# Mach_dieu_khien_tu_xa.net
KiCad netlist of a schematic drawn in Altium Designer
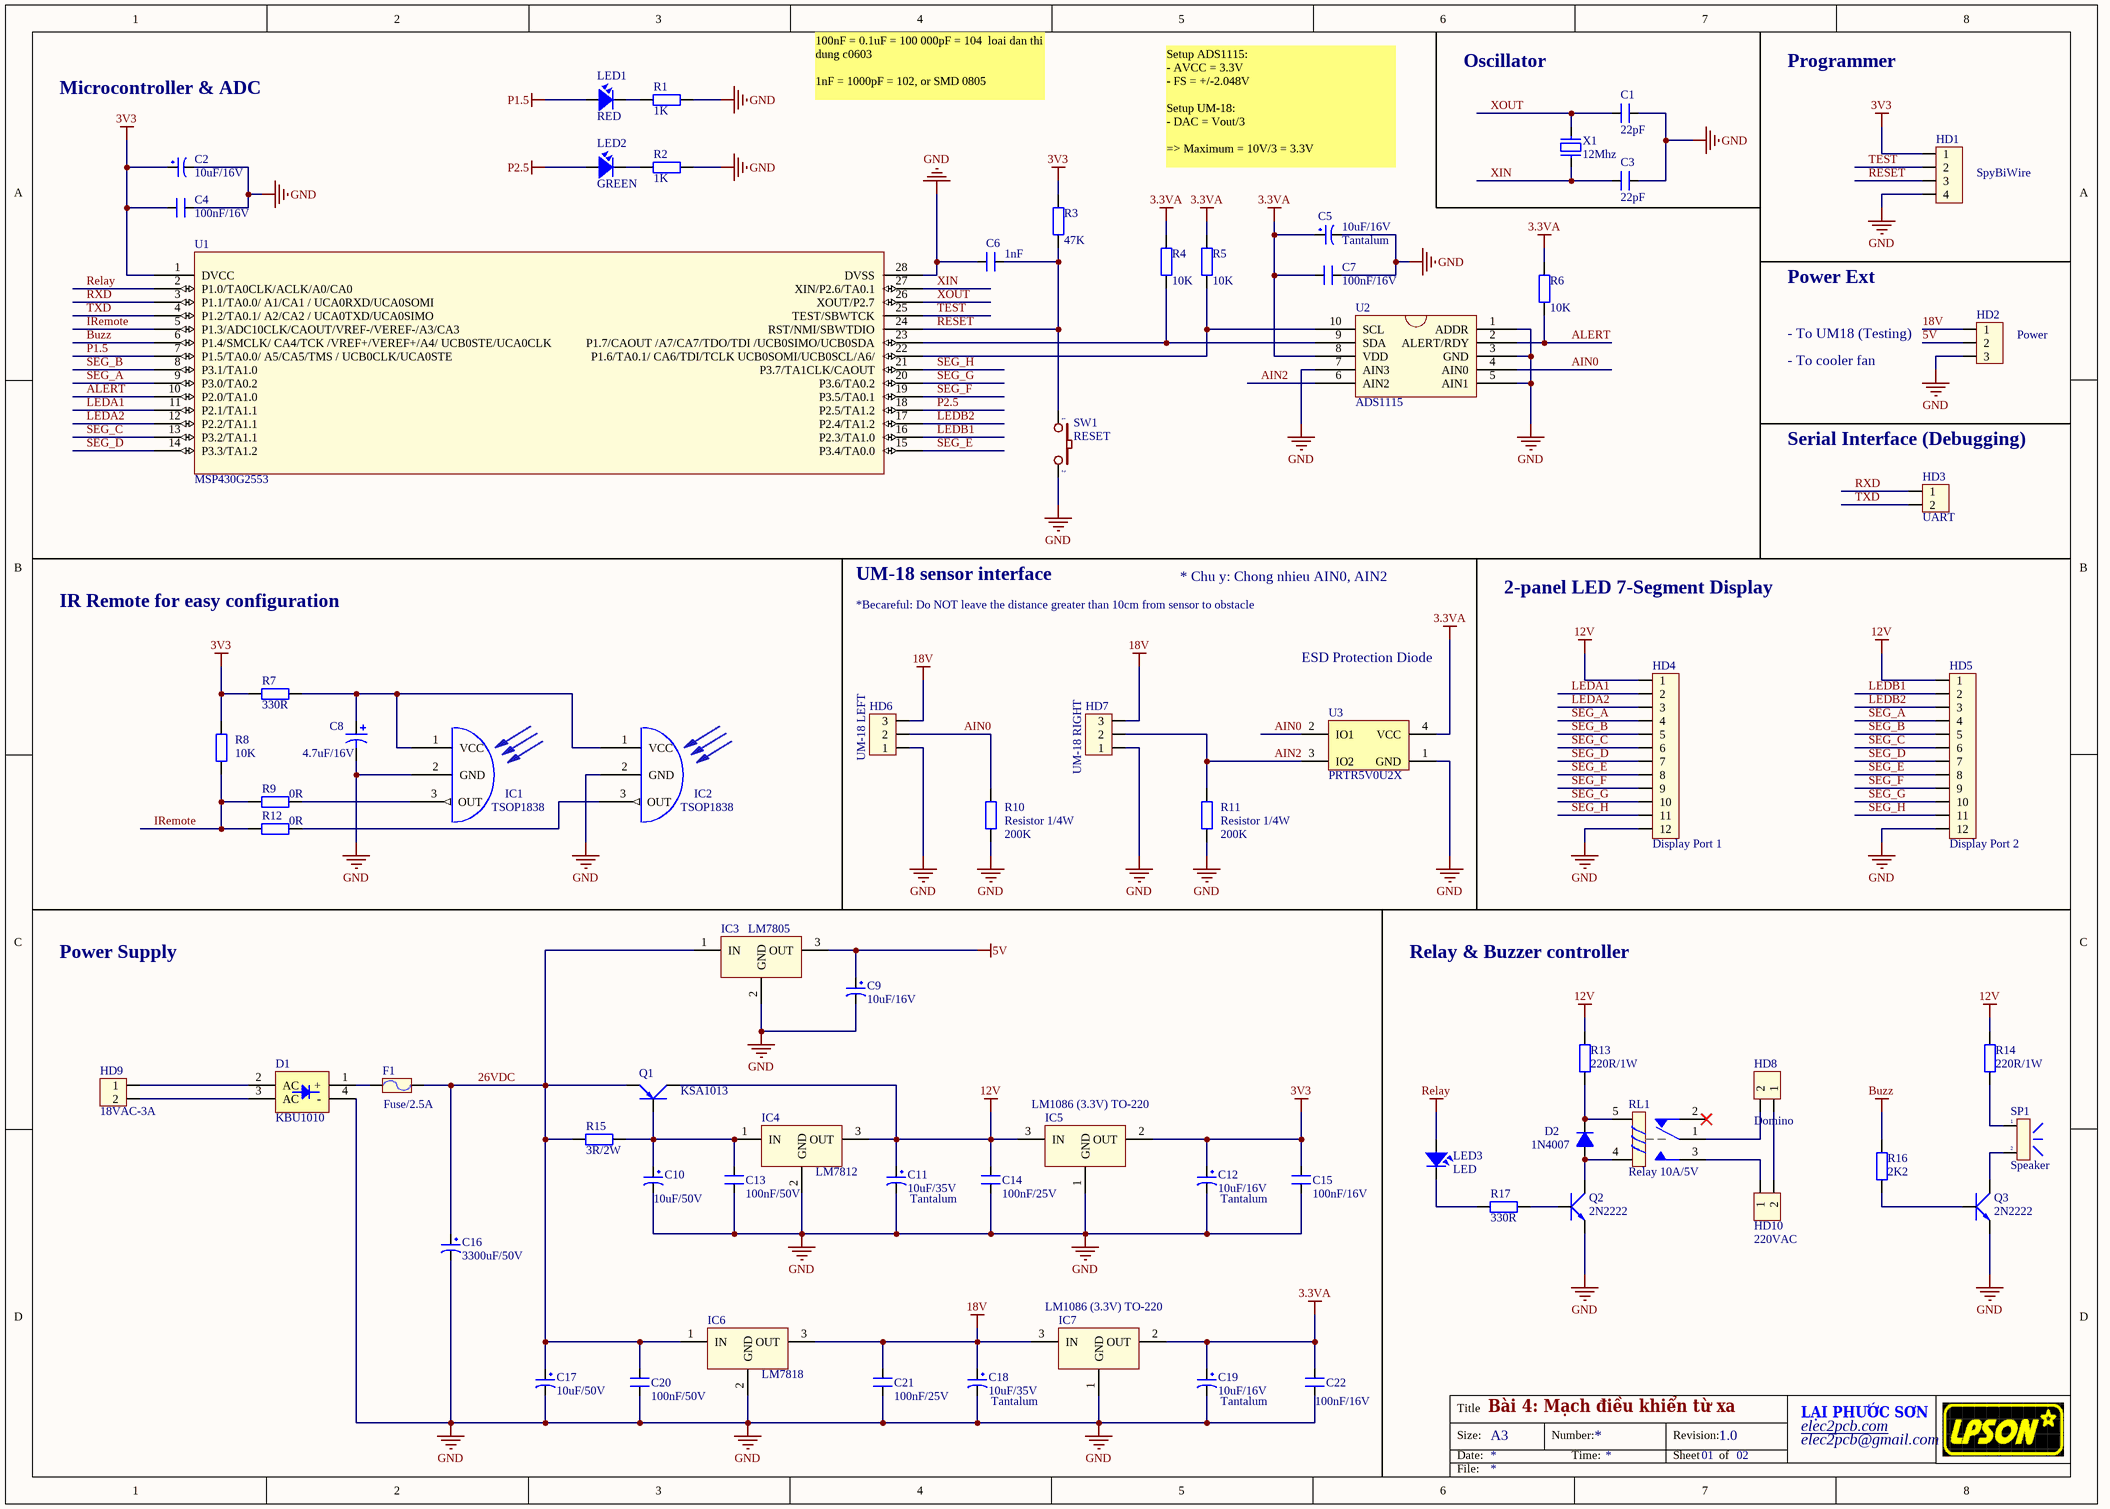
[diagram p0: Mach dieu khien tu xa.SchDoc]

(export (version "E")
  (design (tool "Eeschema 10.0.6"))
  (components
    (comp (ref "C1")
      (value "22pF")
      (footprint "C0603")
      (description "0805-SMD Capacitor")
      (libsource (lib "syhaunguyen") (part "CN1"))
    )
    (comp (ref "C2")
      (value "10uF/16V")
      (footprint "C0805")
      (description "Cap P  0,1uF < 22uF , 16 - 50V")
      (libsource (lib "") (part "CP1_1"))
    )
    (comp (ref "C3")
      (value "22pF")
      (footprint "C0603")
      (description "0805-SMD Capacitor")
      (libsource (lib "syhaunguyen") (part "CN1"))
    )
    (comp (ref "C4")
      (value "100nF/16V")
      (footprint "Tu gom 104")
      (description "Cap np 104 => 105pF")
      (libsource (lib "VNELEK") (part "CN2"))
    )
    (comp (ref "C5")
      (value "10uF/16V")
      (footprint "CAP_TANTA_10UF_16V")
      (description "Tantalum Capacitor")
      (fields (field (name "TYPE") "Tantalum"))
      (libsource (lib "") (part "CP1_1"))
    )
    (comp (ref "C6")
      (value "1nF")
      (footprint "C0805")
      (description "Cap np 104 => 105pF")
      (libsource (lib "VNELEK") (part "CN2"))
    )
    (comp (ref "C7")
      (value "100nF/16V")
      (footprint "Tu gom 104")
      (description "Cap np 104 => 105pF")
      (libsource (lib "VNELEK") (part "CN2"))
    )
    (comp (ref "C8")
      (value "4.7uF/16V")
      (footprint "C0805")
      (description "Polarized Capacitor (Radial)")
      (fields (field (name "Comment") "Cap Pol1") (field (name "PUBLISHER") "Altium Limited"))
      (libsource (lib "Miscellaneous Devices") (part "Cap Pol1"))
    )
    (comp (ref "C9")
      (value "10uF/16V")
      (footprint "CAP_10UF_16V")
      (description "Aluminium Capacitor")
      (libsource (lib "VNELEK") (part "CP1"))
    )
    (comp (ref "C10")
      (value "10uF/50V")
      (footprint "C_FC_10UF_50V")
      (description "Aluminium Capacitor")
      (libsource (lib "VNELEK") (part "CP1"))
    )
    (comp (ref "C11")
      (value "10uF/35V")
      (footprint "CAP_TANTA_10UF_35V")
      (description "Tantalum Capacitor")
      (fields (field (name "TYPE") "Tantalum"))
      (libsource (lib "VNELEK") (part "CP1"))
    )
    (comp (ref "C12")
      (value "10uF/16V")
      (footprint "CAP_TANTA_10UF_16V")
      (description "Tantalum Capacitor")
      (fields (field (name "TYPE") "Tantalum"))
      (libsource (lib "VNELEK") (part "CP1"))
    )
    (comp (ref "C13")
      (value "100nF/50V")
      (footprint "Tu gom 104")
      (description "Cap np 104 => 105pF")
      (libsource (lib "VNELEK") (part "CN2"))
    )
    (comp (ref "C14")
      (value "100nF/25V")
      (footprint "Tu gom 104")
      (description "Cap np 104 => 105pF")
      (libsource (lib "VNELEK") (part "CN2"))
    )
    (comp (ref "C15")
      (value "100nF/16V")
      (footprint "Tu gom 104")
      (description "Cap np 104 => 105pF")
      (libsource (lib "VNELEK") (part "CN2"))
    )
    (comp (ref "C16")
      (value "3300uF/50V")
      (footprint "CAP_3300UF_50V")
      (description "Cap P  0,1uF < 22uF , 16 - 50V")
      (libsource (lib "VNELEK") (part "CP1"))
    )
    (comp (ref "C17")
      (value "10uF/50V")
      (footprint "C_FC_10UF_50V")
      (description "Aluminium Capacitor")
      (libsource (lib "VNELEK") (part "CP1"))
    )
    (comp (ref "C18")
      (value "10uF/35V")
      (footprint "CAP_TANTA_10UF_35V")
      (description "Tantalum Capacitor")
      (fields (field (name "TYPE") "Tantalum"))
      (libsource (lib "VNELEK") (part "CP1"))
    )
    (comp (ref "C19")
      (value "10uF/16V")
      (footprint "CAP_TANTA_10UF_16V")
      (description "Tantalum Capacitor")
      (fields (field (name "TYPE") "Tantalum"))
      (libsource (lib "VNELEK") (part "CP1"))
    )
    (comp (ref "C20")
      (value "100nF/50V")
      (footprint "Tu gom 104")
      (description "Cap np 104 => 105pF")
      (libsource (lib "VNELEK") (part "CN2"))
    )
    (comp (ref "C21")
      (value "100nF/25V")
      (footprint "Tu gom 104")
      (description "Cap np 104 => 105pF")
      (libsource (lib "VNELEK") (part "CN2"))
    )
    (comp (ref "C22")
      (value "100nF/16V")
      (footprint "Tu gom 104")
      (description "Cap np 104 => 105pF")
      (libsource (lib "VNELEK") (part "CN2"))
    )
    (comp (ref "D1")
      (value "KBU1010")
      (footprint "KBU1010G")
      (description "10A glass passivated bridge rectifier")
      (libsource (lib "Tran Tuan") (part "KBU1010"))
    )
    (comp (ref "D2")
      (value "1N4007")
      (footprint "1N4007")
      (description "Diode 1A")
      (libsource (lib "VNELEK") (part "D1A"))
    )
    (comp (ref "F1")
      (value "Fuse/2.5A")
      (footprint "FUSE2_5A")
      (description "Fuse")
      (fields (field (name "DESIGNED BY") "VanDungEvn"))
      (libsource (lib "VNELEK") (part "Fuse"))
    )
    (comp (ref "HD1")
      (value "SpyBiWire")
      (footprint "Header_4")
      (description "Header 4 (Green)")
      (libsource (lib "VNELEK") (part "Hed4"))
    )
    (comp (ref "HD2")
      (value "Power")
      (footprint "CON3")
      (description "Header 3 (Green)")
      (libsource (lib "") (part "Hed3_1"))
    )
    (comp (ref "HD3")
      (value "UART")
      (footprint "Header_2")
      (description "Header 2 (Green)")
      (libsource (lib "") (part "Hed2_2"))
    )
    (comp (ref "HD4")
      (value "Display Port 1")
      (footprint "CON12")
      (description "Header 12")
      (libsource (lib "Tran Tuan") (part "Hed12"))
    )
    (comp (ref "HD5")
      (value "Display Port 2")
      (footprint "CON12")
      (description "Header 12")
      (libsource (lib "Tran Tuan") (part "Hed12"))
    )
    (comp (ref "HD6")
      (value "UM-18 LEFT")
      (footprint "CON3")
      (description "Header 3 (Green)")
      (libsource (lib "VNELEK") (part "Hed3"))
    )
    (comp (ref "HD7")
      (value "UM-18 RIGHT")
      (footprint "CON3")
      (description "Header 3 (Green)")
      (libsource (lib "VNELEK") (part "Hed3"))
    )
    (comp (ref "HD8")
      (value "Domino")
      (footprint "DOMINO2_GREEN")
      (description "Header 2 (Green)")
      (libsource (lib "") (part "Hed2_2"))
    )
    (comp (ref "HD9")
      (value "18VAC-3A")
      (footprint "DOMINO2_GREEN")
      (description "Header 2 (Green)")
      (libsource (lib "") (part "Hed2_1"))
    )
    (comp (ref "HD10")
      (value "220VAC")
      (footprint "DOMINO2_GREEN")
      (description "Header 2 (Green)")
      (libsource (lib "VNELEK") (part "Hed2"))
    )
    (comp (ref "IC1")
      (value "TSOP1838")
      (footprint "TSOP1838")
      (libsource (lib "Tran Tuan") (part "TSOP1838"))
    )
    (comp (ref "IC2")
      (value "TSOP1838")
      (footprint "TSOP1838")
      (libsource (lib "Tran Tuan") (part "TSOP1838"))
    )
    (comp (ref "IC3")
      (value "LM7805")
      (footprint "LM7805")
      (description "Linear Regulator")
      (libsource (lib "VNELEK") (part "LM78xx"))
    )
    (comp (ref "IC4")
      (value "LM7812")
      (footprint "LM7805")
      (description "Linear Regulator")
      (fields (field (name "MANUFACTURER") "Fairchild Semiconductor"))
      (libsource (lib "VNELEK") (part "LM78xx"))
    )
    (comp (ref "IC5")
      (value "LM1086 (3.3V) TO-220")
      (footprint "LM1086")
      (description "Linear Regulator")
      (libsource (lib "") (part "LM78xx_1"))
    )
    (comp (ref "IC6")
      (value "LM7818")
      (footprint "LM7805")
      (description "Linear Regulator")
      (libsource (lib "VNELEK") (part "LM78xx"))
    )
    (comp (ref "IC7")
      (value "LM1086 (3.3V) TO-220")
      (footprint "LM1086")
      (description "Linear Regulator")
      (libsource (lib "") (part "LM78xx_1"))
    )
    (comp (ref "LED1")
      (value "RED")
      (footprint "LED3R")
      (description "LED Single colour Green and Red")
      (libsource (lib "VNELEK") (part "LED"))
    )
    (comp (ref "LED2")
      (value "GREEN")
      (footprint "LED3R")
      (description "LED Single colour Green and Red")
      (libsource (lib "VNELEK") (part "LED"))
    )
    (comp (ref "LED3")
      (value "LED")
      (footprint "LED3R")
      (description "LED Single colour Green and Red")
      (libsource (lib "VNELEK") (part "LED"))
    )
    (comp (ref "Q1")
      (value "KSA1013")
      (footprint "KSA1013")
      (description "PNP 600mW, ECB")
      (fields (field (name "MANUFACTURER") "Fairchild Semiconductor"))
      (libsource (lib "VNELEK") (part "A1015"))
    )
    (comp (ref "Q2")
      (value "2N2222")
      (footprint "2N2222")
      (description "TRANS GP SS NPN LP 40V TO92")
      (libsource (lib "VNELEK") (part "C1815"))
    )
    (comp (ref "Q3")
      (value "2N2222")
      (footprint "2N2222")
      (description "TRANS GP SS NPN LP 40V TO92")
      (libsource (lib "VNELEK") (part "C1815"))
    )
    (comp (ref "R1")
      (value "1K")
      (footprint "RESC2012(0805)")
      (description "Resistor")
      (fields (field (name "Comment") "Res2") (field (name "PUBLISHER") "Altium Limited"))
      (libsource (lib "Miscellaneous Devices") (part "Res2"))
    )
    (comp (ref "R2")
      (value "1K")
      (footprint "RESC2012(0805)")
      (description "Resistor")
      (fields (field (name "Comment") "Res2") (field (name "PUBLISHER") "Altium Limited"))
      (libsource (lib "Miscellaneous Devices") (part "Res2"))
    )
    (comp (ref "R3")
      (value "47K")
      (footprint "RESC2012(0805)")
      (description "Resistor")
      (fields (field (name "Comment") "Res2") (field (name "PUBLISHER") "Altium Limited"))
      (libsource (lib "") (part "Res2_2"))
    )
    (comp (ref "R4")
      (value "10K")
      (footprint "RESC2012(0805)")
      (description "Resistor")
      (fields (field (name "Comment") "Res2") (field (name "PUBLISHER") "Altium Limited"))
      (libsource (lib "") (part "Res2_2"))
    )
    (comp (ref "R5")
      (value "10K")
      (footprint "RESC2012(0805)")
      (description "Resistor")
      (fields (field (name "Comment") "Res2") (field (name "PUBLISHER") "Altium Limited"))
      (libsource (lib "") (part "Res2_2"))
    )
    (comp (ref "R6")
      (value "10K")
      (footprint "RESC2012(0805)")
      (description "Resistor")
      (fields (field (name "Comment") "Res2") (field (name "PUBLISHER") "Altium Limited"))
      (libsource (lib "") (part "Res2_2"))
    )
    (comp (ref "R7")
      (value "330R")
      (footprint "RESC2012(0805)")
      (description "Resistor")
      (fields (field (name "Comment") "Res2") (field (name "PUBLISHER") "Altium Limited"))
      (libsource (lib "Miscellaneous Devices") (part "Res2"))
    )
    (comp (ref "R8")
      (value "10K")
      (footprint "RESC2012(0805)")
      (description "Resistor")
      (fields (field (name "Comment") "Res2") (field (name "PUBLISHER") "Altium Limited"))
      (libsource (lib "") (part "Res2_2"))
    )
    (comp (ref "R9")
      (value "0R")
      (footprint "RESC2012(0805)")
      (description "Resistor")
      (fields (field (name "Comment") "Res2") (field (name "PUBLISHER") "Altium Limited"))
      (libsource (lib "Miscellaneous Devices") (part "Res2"))
    )
    (comp (ref "R10")
      (value "Resistor 1/4W")
      (footprint "RESC2012(0805)")
      (fields (field (name "ALTIUM_VALUE") "200K"))
      (libsource (lib "") (part "Res2_1"))
    )
    (comp (ref "R11")
      (value "Resistor 1/4W")
      (footprint "RESC2012(0805)")
      (fields (field (name "ALTIUM_VALUE") "200K"))
      (libsource (lib "") (part "Res2_1"))
    )
    (comp (ref "R12")
      (value "0R")
      (footprint "RESC2012(0805)")
      (description "Resistor")
      (fields (field (name "Comment") "Res2") (field (name "PUBLISHER") "Altium Limited"))
      (libsource (lib "Miscellaneous Devices") (part "Res2"))
    )
    (comp (ref "R13")
      (value "220R/1W")
      (footprint "CFR1WS")
      (description "Resistor")
      (fields (field (name "Comment") "Res2") (field (name "PUBLISHER") "Altium Limited"))
      (libsource (lib "") (part "Res2_1"))
    )
    (comp (ref "R14")
      (value "220R/1W")
      (footprint "CFR1WS")
      (description "Resistor")
      (fields (field (name "Comment") "Res2") (field (name "PUBLISHER") "Altium Limited"))
      (libsource (lib "") (part "Res2_1"))
    )
    (comp (ref "R15")
      (value "3R/2W")
      (footprint "R2WD")
      (description "Resistor")
      (fields (field (name "Comment") "Res2") (field (name "PUBLISHER") "Altium Limited"))
      (libsource (lib "Miscellaneous Devices") (part "Res2"))
    )
    (comp (ref "R16")
      (value "2K2")
      (footprint "RES 1/4W CFR25")
      (description "Resistor")
      (fields (field (name "Comment") "Res2") (field (name "PUBLISHER") "Altium Limited"))
      (libsource (lib "") (part "Res2_1"))
    )
    (comp (ref "R17")
      (value "330R")
      (footprint "RES 1/4W CFR25")
      (description "Resistor")
      (fields (field (name "Comment") "Res2") (field (name "PUBLISHER") "Altium Limited"))
      (libsource (lib "Miscellaneous Devices") (part "Res2"))
    )
    (comp (ref "RL1")
      (value "Relay 10A/5V")
      (footprint "RL_10A_5V")
      (description "Relay SPDT,10A - 12VDC 5 Pin")
      (libsource (lib "VNELEK") (part "Relay 1"))
    )
    (comp (ref "SP1")
      (value "Speaker")
      (footprint "SPEAKER")
      (description "Speaker Chip")
      (libsource (lib "VNELEK") (part "SPK"))
    )
    (comp (ref "SW1")
      (value "RESET")
      (footprint "BUTTON 2PIN TRON")
      (description "Switch button 2 pin")
      (libsource (lib "VNELEK") (part "SW2"))
    )
    (comp (ref "U1")
      (value "MSP430G2553")
      (footprint "MSP430G2253IPW28R")
      (description "MSP430G2553 (28 pins)")
      (libsource (lib "Tran Tuan") (part "MSP430G2553"))
    )
    (comp (ref "U2")
      (value "ADS1115")
      (footprint "ADS1115")
      (description "Analog to Digital Converter")
      (libsource (lib "Tran Tuan") (part "ADS1115"))
    )
    (comp (ref "U3")
      (value "PRTR5V0U2X")
      (footprint "PRTR5V0U2X")
      (description "ESD protection diode")
      (libsource (lib "Tran Tuan") (part "PRTR5V0U2X"))
    )
    (comp (ref "X1")
      (value "12Mhz")
      (footprint "CRYSTAL")
      (description "Crystal For all Crystal 2pin.")
      (libsource (lib "syhaunguyen") (part "XT2"))
    )
  )
  (nets
    (net (code "1") (name "/26VDC") (class "Default")
      (node (ref "C16") (pin "1") (pinfunction "1_1") (pintype "passive"))
      (node (ref "C17") (pin "1") (pinfunction "1_1") (pintype "passive"))
      (node (ref "C20") (pin "2") (pinfunction "2_2") (pintype "passive"))
      (node (ref "F1") (pin "2") (pinfunction "2_2") (pintype "passive"))
      (node (ref "IC3") (pin "1") (pinfunction "IN_1") (pintype "passive"))
      (node (ref "IC6") (pin "1") (pinfunction "IN_1") (pintype "passive"))
      (node (ref "Q1") (pin "1") (pinfunction "E_1") (pintype "passive"))
      (node (ref "R15") (pin "2") (pinfunction "2_2") (pintype "passive"))
    )
    (net (code "2") (name "/AIN0") (class "Default")
      (node (ref "HD6") (pin "2") (pinfunction "2_2") (pintype "passive"))
      (node (ref "R10") (pin "1") (pinfunction "1_1") (pintype "passive"))
      (node (ref "U2") (pin "4") (pinfunction "AIN0_4") (pintype "passive"))
      (node (ref "U3") (pin "2") (pinfunction "IO1_2") (pintype "passive"))
    )
    (net (code "3") (name "/AIN2") (class "Default")
      (node (ref "HD7") (pin "2") (pinfunction "2_2") (pintype "passive"))
      (node (ref "R11") (pin "1") (pinfunction "1_1") (pintype "passive"))
      (node (ref "U2") (pin "6") (pinfunction "AIN2_6") (pintype "passive"))
      (node (ref "U3") (pin "3") (pinfunction "IO2_3") (pintype "passive"))
    )
    (net (code "4") (name "/ALERT") (class "Default")
      (node (ref "R6") (pin "1") (pinfunction "1_1") (pintype "passive"))
      (node (ref "U1") (pin "10") (pinfunction "P2.0/TA1.0_10") (pintype "bidirectional"))
      (node (ref "U2") (pin "2") (pinfunction "ALERT/RDY_2") (pintype "passive"))
    )
    (net (code "5") (name "/IRemote") (class "Default")
      (node (ref "R12") (pin "2") (pinfunction "2_2") (pintype "passive"))
      (node (ref "R8") (pin "1") (pinfunction "1_1") (pintype "passive"))
      (node (ref "R9") (pin "2") (pinfunction "2_2") (pintype "passive"))
      (node (ref "U1") (pin "5") (pinfunction "P1.3/ADC10CLK/CAOUT/VREF-/VEREF-/A3/CA3_5") (pintype "bidirectional"))
    )
    (net (code "6") (name "/LEDA1") (class "Default")
      (node (ref "HD4") (pin "2") (pinfunction "2_2") (pintype "passive"))
      (node (ref "U1") (pin "11") (pinfunction "P2.1/TA1.1_11") (pintype "bidirectional"))
    )
    (net (code "7") (name "/LEDA2") (class "Default")
      (node (ref "HD4") (pin "3") (pinfunction "3_3") (pintype "passive"))
      (node (ref "U1") (pin "12") (pinfunction "P2.2/TA1.1_12") (pintype "bidirectional"))
    )
    (net (code "8") (name "/LEDB1") (class "Default")
      (node (ref "HD5") (pin "2") (pinfunction "2_2") (pintype "passive"))
      (node (ref "U1") (pin "16") (pinfunction "P2.3/TA1.0_16") (pintype "bidirectional"))
    )
    (net (code "9") (name "/LEDB2") (class "Default")
      (node (ref "HD5") (pin "3") (pinfunction "3_3") (pintype "passive"))
      (node (ref "U1") (pin "17") (pinfunction "P2.4/TA1.2_17") (pintype "bidirectional"))
    )
    (net (code "10") (name "/RESET") (class "Default")
      (node (ref "C6") (pin "2") (pinfunction "2_2") (pintype "passive"))
      (node (ref "HD1") (pin "3") (pinfunction "3_3") (pintype "passive"))
      (node (ref "R3") (pin "1") (pinfunction "1_1") (pintype "passive"))
      (node (ref "SW1") (pin "1") (pinfunction "1_1") (pintype "passive"))
      (node (ref "U1") (pin "24") (pinfunction "RST/NMI/SBWTDIO_24") (pintype "passive"))
    )
    (net (code "11") (name "/RXD") (class "Default")
      (node (ref "HD3") (pin "1") (pinfunction "1_1") (pintype "passive"))
      (node (ref "U1") (pin "3") (pinfunction "P1.1/TA0.0/_A1/CA1_/_UCA0RXD/UCA0SOMI_3") (pintype "bidirectional"))
    )
    (net (code "12") (name "/SEG_A") (class "Default")
      (node (ref "HD4") (pin "4") (pinfunction "4_4") (pintype "passive"))
      (node (ref "HD5") (pin "4") (pinfunction "4_4") (pintype "passive"))
      (node (ref "U1") (pin "9") (pinfunction "P3.0/TA0.2_9") (pintype "bidirectional"))
    )
    (net (code "13") (name "/SEG_B") (class "Default")
      (node (ref "HD4") (pin "5") (pinfunction "5_5") (pintype "passive"))
      (node (ref "HD5") (pin "5") (pinfunction "5_5") (pintype "passive"))
      (node (ref "U1") (pin "8") (pinfunction "P3.1/TA1.0_8") (pintype "bidirectional"))
    )
    (net (code "14") (name "/SEG_C") (class "Default")
      (node (ref "HD4") (pin "6") (pinfunction "6_6") (pintype "passive"))
      (node (ref "HD5") (pin "6") (pinfunction "6_6") (pintype "passive"))
      (node (ref "U1") (pin "13") (pinfunction "P3.2/TA1.1_13") (pintype "bidirectional"))
    )
    (net (code "15") (name "/SEG_D") (class "Default")
      (node (ref "HD4") (pin "7") (pinfunction "7_7") (pintype "passive"))
      (node (ref "HD5") (pin "7") (pinfunction "7_7") (pintype "passive"))
      (node (ref "U1") (pin "14") (pinfunction "P3.3/TA1.2_14") (pintype "bidirectional"))
    )
    (net (code "16") (name "/SEG_E") (class "Default")
      (node (ref "HD4") (pin "8") (pinfunction "8_8") (pintype "passive"))
      (node (ref "HD5") (pin "8") (pinfunction "8_8") (pintype "passive"))
      (node (ref "U1") (pin "15") (pinfunction "P3.4/TA0.0_15") (pintype "bidirectional"))
    )
    (net (code "17") (name "/SEG_F") (class "Default")
      (node (ref "HD4") (pin "9") (pinfunction "9_9") (pintype "passive"))
      (node (ref "HD5") (pin "9") (pinfunction "9_9") (pintype "passive"))
      (node (ref "U1") (pin "19") (pinfunction "P3.5/TA0.1_19") (pintype "bidirectional"))
    )
    (net (code "18") (name "/SEG_G") (class "Default")
      (node (ref "HD4") (pin "10") (pinfunction "10_10") (pintype "passive"))
      (node (ref "HD5") (pin "10") (pinfunction "10_10") (pintype "passive"))
      (node (ref "U1") (pin "20") (pinfunction "P3.6/TA0.2_20") (pintype "bidirectional"))
    )
    (net (code "19") (name "/SEG_H") (class "Default")
      (node (ref "HD4") (pin "11") (pinfunction "11_11") (pintype "passive"))
      (node (ref "HD5") (pin "11") (pinfunction "11_11") (pintype "passive"))
      (node (ref "U1") (pin "21") (pinfunction "P3.7/TA1CLK/CAOUT_21") (pintype "bidirectional"))
    )
    (net (code "20") (name "/TEST") (class "Default")
      (node (ref "HD1") (pin "2") (pinfunction "2_2") (pintype "passive"))
      (node (ref "U1") (pin "25") (pinfunction "TEST/SBWTCK_25") (pintype "passive"))
    )
    (net (code "21") (name "/TXD") (class "Default")
      (node (ref "HD3") (pin "2") (pinfunction "2_2") (pintype "passive"))
      (node (ref "U1") (pin "4") (pinfunction "P1.2/TA0.1/_A2/CA2_/_UCA0TXD/UCA0SIMO_4") (pintype "bidirectional"))
    )
    (net (code "22") (name "/XIN") (class "Default")
      (node (ref "C3") (pin "2") (pinfunction "2_2") (pintype "passive"))
      (node (ref "U1") (pin "27") (pinfunction "XIN/P2.6/TA0.1_27") (pintype "bidirectional"))
      (node (ref "X1") (pin "2") (pinfunction "2_2") (pintype "passive"))
    )
    (net (code "23") (name "/XOUT") (class "Default")
      (node (ref "C1") (pin "2") (pinfunction "2_2") (pintype "passive"))
      (node (ref "U1") (pin "26") (pinfunction "XOUT/P2.7_26") (pintype "bidirectional"))
      (node (ref "X1") (pin "1") (pinfunction "1_1") (pintype "passive"))
    )
    (net (code "24") (name "3.3VA") (class "Default")
      (node (ref "C19") (pin "1") (pinfunction "1_1") (pintype "passive"))
      (node (ref "C22") (pin "2") (pinfunction "2_2") (pintype "passive"))
      (node (ref "C5") (pin "1") (pinfunction "1_1") (pintype "passive"))
      (node (ref "C7") (pin "2") (pinfunction "2_2") (pintype "passive"))
      (node (ref "IC7") (pin "2") (pinfunction "OUT_2") (pintype "passive"))
      (node (ref "R4") (pin "2") (pinfunction "2_2") (pintype "passive"))
      (node (ref "R5") (pin "2") (pinfunction "2_2") (pintype "passive"))
      (node (ref "R6") (pin "2") (pinfunction "2_2") (pintype "passive"))
      (node (ref "U2") (pin "8") (pinfunction "VDD_8") (pintype "passive"))
      (node (ref "U3") (pin "4") (pinfunction "VCC_4") (pintype "passive"))
    )
    (net (code "25") (name "3V3") (class "Default")
      (node (ref "C12") (pin "1") (pinfunction "1_1") (pintype "passive"))
      (node (ref "C15") (pin "2") (pinfunction "2_2") (pintype "passive"))
      (node (ref "C2") (pin "1") (pinfunction "1_1") (pintype "passive"))
      (node (ref "C4") (pin "2") (pinfunction "2_2") (pintype "passive"))
      (node (ref "HD1") (pin "1") (pinfunction "1_1") (pintype "passive"))
      (node (ref "IC5") (pin "2") (pinfunction "OUT_2") (pintype "passive"))
      (node (ref "R3") (pin "2") (pinfunction "2_2") (pintype "passive"))
      (node (ref "R7") (pin "2") (pinfunction "2_2") (pintype "passive"))
      (node (ref "R8") (pin "2") (pinfunction "2_2") (pintype "passive"))
      (node (ref "U1") (pin "1") (pinfunction "DVCC_1") (pintype "power_in"))
    )
    (net (code "26") (name "5V") (class "Default")
      (node (ref "C9") (pin "1") (pinfunction "1_1") (pintype "passive"))
      (node (ref "HD2") (pin "2") (pinfunction "2_2") (pintype "passive"))
      (node (ref "IC3") (pin "3") (pinfunction "OUT_3") (pintype "passive"))
    )
    (net (code "27") (name "12V") (class "Default")
      (node (ref "C11") (pin "1") (pinfunction "1_1") (pintype "passive"))
      (node (ref "C14") (pin "2") (pinfunction "2_2") (pintype "passive"))
      (node (ref "HD4") (pin "1") (pinfunction "1_1") (pintype "passive"))
      (node (ref "HD5") (pin "1") (pinfunction "1_1") (pintype "passive"))
      (node (ref "IC4") (pin "3") (pinfunction "OUT_3") (pintype "passive"))
      (node (ref "IC5") (pin "3") (pinfunction "IN_3") (pintype "passive"))
      (node (ref "Q1") (pin "2") (pinfunction "C_2") (pintype "passive"))
      (node (ref "R13") (pin "1") (pinfunction "1_1") (pintype "passive"))
      (node (ref "R14") (pin "1") (pinfunction "1_1") (pintype "passive"))
    )
    (net (code "28") (name "18V") (class "Default")
      (node (ref "C18") (pin "1") (pinfunction "1_1") (pintype "passive"))
      (node (ref "C21") (pin "2") (pinfunction "2_2") (pintype "passive"))
      (node (ref "HD2") (pin "1") (pinfunction "1_1") (pintype "passive"))
      (node (ref "HD6") (pin "3") (pinfunction "3_3") (pintype "passive"))
      (node (ref "HD7") (pin "3") (pinfunction "3_3") (pintype "passive"))
      (node (ref "IC6") (pin "3") (pinfunction "OUT_3") (pintype "passive"))
      (node (ref "IC7") (pin "3") (pinfunction "IN_3") (pintype "passive"))
    )
    (net (code "29") (name "Buzz") (class "Default")
      (node (ref "R16") (pin "1") (pinfunction "1_1") (pintype "passive"))
      (node (ref "U1") (pin "6") (pinfunction "P1.4/SMCLK/_CA4/TCK_/VREF+/VEREF+/A4/_UCB0STE/UCA0CLK_6") (pintype "bidirectional"))
    )
    (net (code "30") (name "GND") (class "Default")
      (node (ref "C1") (pin "1") (pinfunction "1_1") (pintype "passive"))
      (node (ref "C10") (pin "2") (pinfunction "2_2") (pintype "passive"))
      (node (ref "C11") (pin "2") (pinfunction "2_2") (pintype "passive"))
      (node (ref "C12") (pin "2") (pinfunction "2_2") (pintype "passive"))
      (node (ref "C13") (pin "1") (pinfunction "1_1") (pintype "passive"))
      (node (ref "C14") (pin "1") (pinfunction "1_1") (pintype "passive"))
      (node (ref "C15") (pin "1") (pinfunction "1_1") (pintype "passive"))
      (node (ref "C16") (pin "2") (pinfunction "2_2") (pintype "passive"))
      (node (ref "C17") (pin "2") (pinfunction "2_2") (pintype "passive"))
      (node (ref "C18") (pin "2") (pinfunction "2_2") (pintype "passive"))
      (node (ref "C19") (pin "2") (pinfunction "2_2") (pintype "passive"))
      (node (ref "C2") (pin "2") (pinfunction "2_2") (pintype "passive"))
      (node (ref "C20") (pin "1") (pinfunction "1_1") (pintype "passive"))
      (node (ref "C21") (pin "1") (pinfunction "1_1") (pintype "passive"))
      (node (ref "C22") (pin "1") (pinfunction "1_1") (pintype "passive"))
      (node (ref "C3") (pin "1") (pinfunction "1_1") (pintype "passive"))
      (node (ref "C4") (pin "1") (pinfunction "1_1") (pintype "passive"))
      (node (ref "C5") (pin "2") (pinfunction "2_2") (pintype "passive"))
      (node (ref "C6") (pin "1") (pinfunction "1_1") (pintype "passive"))
      (node (ref "C7") (pin "1") (pinfunction "1_1") (pintype "passive"))
      (node (ref "C8") (pin "2") (pinfunction "2_2") (pintype "passive"))
      (node (ref "C9") (pin "2") (pinfunction "2_2") (pintype "passive"))
      (node (ref "D1") (pin "4") (pinfunction "-_4") (pintype "power_in"))
      (node (ref "HD1") (pin "4") (pinfunction "4_4") (pintype "passive"))
      (node (ref "HD2") (pin "3") (pinfunction "3_3") (pintype "passive"))
      (node (ref "HD4") (pin "12") (pinfunction "12_12") (pintype "passive"))
      (node (ref "HD5") (pin "12") (pinfunction "12_12") (pintype "passive"))
      (node (ref "HD6") (pin "1") (pinfunction "1_1") (pintype "passive"))
      (node (ref "HD7") (pin "1") (pinfunction "1_1") (pintype "passive"))
      (node (ref "IC1") (pin "2") (pinfunction "GND_2") (pintype "power_in"))
      (node (ref "IC2") (pin "2") (pinfunction "GND_2") (pintype "power_in"))
      (node (ref "IC3") (pin "2") (pinfunction "GND_2") (pintype "passive"))
      (node (ref "IC4") (pin "2") (pinfunction "GND_2") (pintype "passive"))
      (node (ref "IC5") (pin "1") (pinfunction "GND_1") (pintype "passive"))
      (node (ref "IC6") (pin "2") (pinfunction "GND_2") (pintype "passive"))
      (node (ref "IC7") (pin "1") (pinfunction "GND_1") (pintype "passive"))
      (node (ref "Q2") (pin "1") (pinfunction "E_1") (pintype "passive"))
      (node (ref "Q3") (pin "1") (pinfunction "E_1") (pintype "passive"))
      (node (ref "R1") (pin "1") (pinfunction "1_1") (pintype "passive"))
      (node (ref "R10") (pin "2") (pinfunction "2_2") (pintype "passive"))
      (node (ref "R11") (pin "2") (pinfunction "2_2") (pintype "passive"))
      (node (ref "R2") (pin "1") (pinfunction "1_1") (pintype "passive"))
      (node (ref "SW1") (pin "2") (pinfunction "2_2") (pintype "passive"))
      (node (ref "U1") (pin "28") (pinfunction "DVSS_28") (pintype "passive"))
      (node (ref "U2") (pin "1") (pinfunction "ADDR_1") (pintype "passive"))
      (node (ref "U2") (pin "3") (pinfunction "GND_3") (pintype "passive"))
      (node (ref "U2") (pin "5") (pinfunction "AIN1_5") (pintype "passive"))
      (node (ref "U2") (pin "7") (pinfunction "AIN3_7") (pintype "passive"))
      (node (ref "U3") (pin "1") (pinfunction "GND_1") (pintype "passive"))
    )
    (net (code "31") (name "Net-(D1-+)") (class "Default")
      (node (ref "D1") (pin "1") (pinfunction "+_1") (pintype "power_in"))
      (node (ref "F1") (pin "1") (pinfunction "1_1") (pintype "passive"))
    )
    (net (code "32") (name "Net-(D1-AC-Pad2)") (class "Default")
      (node (ref "D1") (pin "2") (pinfunction "AC_2") (pintype "power_in"))
      (node (ref "HD9") (pin "1") (pinfunction "1_1") (pintype "passive"))
    )
    (net (code "33") (name "Net-(D1-AC-Pad3)") (class "Default")
      (node (ref "D1") (pin "3") (pinfunction "AC_3") (pintype "power_in"))
      (node (ref "HD9") (pin "2") (pinfunction "2_2") (pintype "passive"))
    )
    (net (code "34") (name "Net-(D2-A)") (class "Default")
      (node (ref "D2") (pin "1") (pinfunction "A_1") (pintype "passive"))
      (node (ref "Q2") (pin "3") (pinfunction "C_3") (pintype "passive"))
      (node (ref "RL1") (pin "4") (pinfunction "4_4") (pintype "passive"))
    )
    (net (code "35") (name "Net-(D2-K)") (class "Default")
      (node (ref "D2") (pin "2") (pinfunction "K_2") (pintype "passive"))
      (node (ref "R13") (pin "2") (pinfunction "2_2") (pintype "passive"))
      (node (ref "RL1") (pin "5") (pinfunction "5_5") (pintype "passive"))
    )
    (net (code "36") (name "Net-(HD8-Pad2)") (class "Default")
      (node (ref "HD8") (pin "2") (pinfunction "2_2") (pintype "passive"))
      (node (ref "RL1") (pin "1") (pinfunction "1_1") (pintype "passive"))
    )
    (net (code "37") (name "Net-(HD10-Pad1)") (class "Default")
      (node (ref "HD10") (pin "1") (pinfunction "1_1") (pintype "passive"))
      (node (ref "RL1") (pin "3") (pinfunction "3_3") (pintype "passive"))
    )
    (net (code "38") (name "Net-(HD10-Pad2)") (class "Default")
      (node (ref "HD10") (pin "2") (pinfunction "2_2") (pintype "passive"))
      (node (ref "HD8") (pin "1") (pinfunction "1_1") (pintype "passive"))
    )
    (net (code "39") (name "Net-(IC1-OUT)") (class "Default")
      (node (ref "IC1") (pin "3") (pinfunction "OUT_3") (pintype "output"))
      (node (ref "R9") (pin "1") (pinfunction "1_1") (pintype "passive"))
    )
    (net (code "40") (name "Net-(IC1-VCC)") (class "Default")
      (node (ref "C8") (pin "1") (pinfunction "1_1") (pintype "passive"))
      (node (ref "IC1") (pin "1") (pinfunction "VCC_1") (pintype "power_in"))
      (node (ref "IC2") (pin "1") (pinfunction "VCC_1") (pintype "power_in"))
      (node (ref "R7") (pin "1") (pinfunction "1_1") (pintype "passive"))
    )
    (net (code "41") (name "Net-(IC2-OUT)") (class "Default")
      (node (ref "IC2") (pin "3") (pinfunction "OUT_3") (pintype "output"))
      (node (ref "R12") (pin "1") (pinfunction "1_1") (pintype "passive"))
    )
    (net (code "42") (name "Net-(IC4-IN)") (class "Default")
      (node (ref "C10") (pin "1") (pinfunction "1_1") (pintype "passive"))
      (node (ref "C13") (pin "2") (pinfunction "2_2") (pintype "passive"))
      (node (ref "IC4") (pin "1") (pinfunction "IN_1") (pintype "passive"))
      (node (ref "Q1") (pin "3") (pinfunction "B_3") (pintype "passive"))
      (node (ref "R15") (pin "1") (pinfunction "1_1") (pintype "passive"))
    )
    (net (code "43") (name "Net-(LED1-Pad2)") (class "Default")
      (node (ref "LED1") (pin "2") (pinfunction "2_2") (pintype "passive"))
      (node (ref "R1") (pin "2") (pinfunction "2_2") (pintype "passive"))
    )
    (net (code "44") (name "Net-(LED2-Pad2)") (class "Default")
      (node (ref "LED2") (pin "2") (pinfunction "2_2") (pintype "passive"))
      (node (ref "R2") (pin "2") (pinfunction "2_2") (pintype "passive"))
    )
    (net (code "45") (name "Net-(LED3-Pad2)") (class "Default")
      (node (ref "LED3") (pin "2") (pinfunction "2_2") (pintype "passive"))
      (node (ref "R17") (pin "2") (pinfunction "2_2") (pintype "passive"))
    )
    (net (code "46") (name "Net-(Q2-B)") (class "Default")
      (node (ref "Q2") (pin "2") (pinfunction "B_2") (pintype "passive"))
      (node (ref "R17") (pin "1") (pinfunction "1_1") (pintype "passive"))
    )
    (net (code "47") (name "Net-(Q3-B)") (class "Default")
      (node (ref "Q3") (pin "2") (pinfunction "B_2") (pintype "passive"))
      (node (ref "R16") (pin "2") (pinfunction "2_2") (pintype "passive"))
    )
    (net (code "48") (name "Net-(Q3-C)") (class "Default")
      (node (ref "Q3") (pin "3") (pinfunction "C_3") (pintype "passive"))
      (node (ref "SP1") (pin "2") (pinfunction "2_2") (pintype "passive"))
    )
    (net (code "49") (name "Net-(R14-Pad2)") (class "Default")
      (node (ref "R14") (pin "2") (pinfunction "2_2") (pintype "passive"))
      (node (ref "SP1") (pin "1") (pinfunction "1_1") (pintype "passive"))
    )
    (net (code "50") (name "Net-(U1-P1.6{slash}TA0.1{slash}_CA6{slash}TDI{slash}TCLK_UCB0SOMI{slash}UCB0SCL{slash}A6{slash})") (class "Default")
      (node (ref "R5") (pin "1") (pinfunction "1_1") (pintype "passive"))
      (node (ref "U1") (pin "22") (pinfunction "P1.6/TA0.1/_CA6/TDI/TCLK_UCB0SOMI/UCB0SCL/A6/_22") (pintype "bidirectional"))
      (node (ref "U2") (pin "10") (pinfunction "SCL_10") (pintype "passive"))
    )
    (net (code "51") (name "Net-(U1-P1.7{slash}CAOUT_{slash}A7{slash}CA7{slash}TDO{slash}TDI_{slash}UCB0SIMO{slash}UCB0SDA)") (class "Default")
      (node (ref "R4") (pin "1") (pinfunction "1_1") (pintype "passive"))
      (node (ref "U1") (pin "23") (pinfunction "P1.7/CAOUT_/A7/CA7/TDO/TDI_/UCB0SIMO/UCB0SDA_23") (pintype "bidirectional"))
      (node (ref "U2") (pin "9") (pinfunction "SDA_9") (pintype "passive"))
    )
    (net (code "52") (name "P1.5") (class "Default")
      (node (ref "LED1") (pin "1") (pinfunction "1_1") (pintype "passive"))
      (node (ref "U1") (pin "7") (pinfunction "P1.5/TA0.0/_A5/CA5/TMS_/_UCB0CLK/UCA0STE_7") (pintype "bidirectional"))
    )
    (net (code "53") (name "P2.5") (class "Default")
      (node (ref "LED2") (pin "1") (pinfunction "1_1") (pintype "passive"))
      (node (ref "U1") (pin "18") (pinfunction "P2.5/TA1.2_18") (pintype "bidirectional"))
    )
    (net (code "54") (name "Relay") (class "Default")
      (node (ref "LED3") (pin "1") (pinfunction "1_1") (pintype "passive"))
      (node (ref "U1") (pin "2") (pinfunction "P1.0/TA0CLK/ACLK/A0/CA0_2") (pintype "bidirectional"))
    )
    (net (code "55") (name "unconnected-(RL1-Pad2)") (class "Default")
      (node (ref "RL1") (pin "2") (pinfunction "2_2") (pintype "passive+no_connect"))
    )
  )
)
